# FPGA_SPI_JTAG_IO.net
KiCad netlist of a schematic drawn in Altium Designer
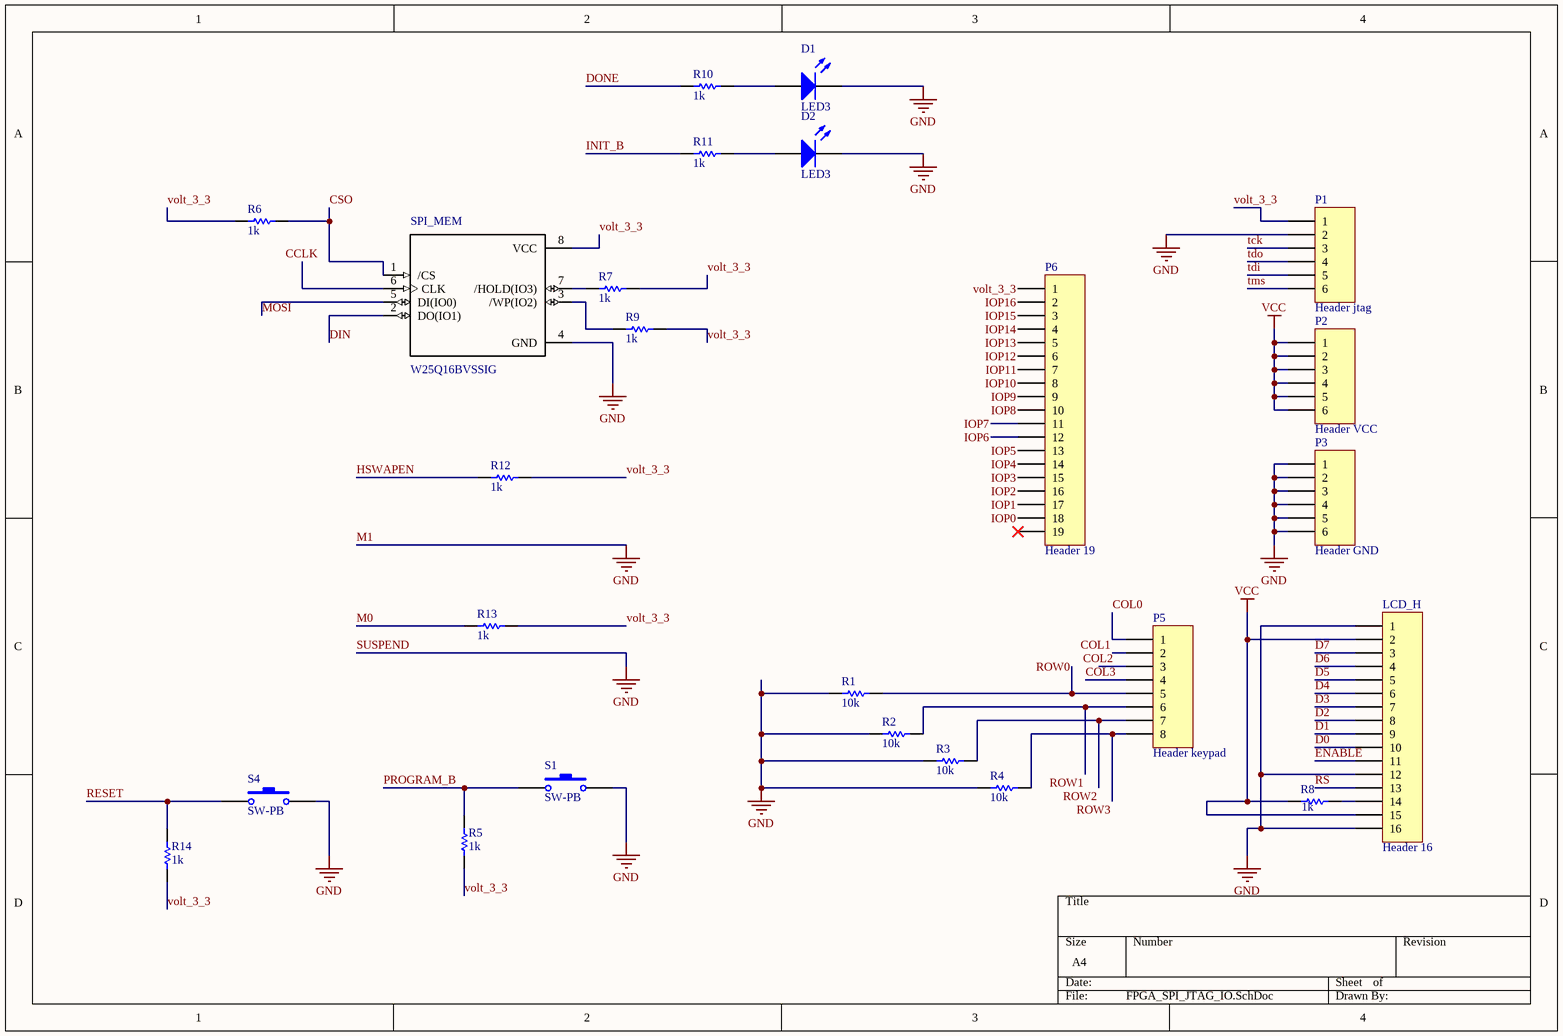
[diagram p0: FPGA_SPI_JTAG_IO.SchDoc]

(export (version "E")
  (design (tool "Eeschema 10.0.6"))
  (components
    (comp (ref "D1")
      (value "LED3")
      (footprint "3.5X2.8X1.9")
      (description "Typical BLUE SiC LED")
      (fields (field (name "PUBLISHER") "Altium Limited"))
      (libsource (lib "Miscellaneous Devices") (part "LED3"))
    )
    (comp (ref "D2")
      (value "LED3")
      (footprint "3.5X2.8X1.9")
      (description "Typical BLUE SiC LED")
      (fields (field (name "PUBLISHER") "Altium Limited"))
      (libsource (lib "Miscellaneous Devices") (part "LED3"))
    )
    (comp (ref "LCD_H")
      (value "Header 16")
      (footprint "HDR1X16")
      (description "Header, 16-Pin")
      (fields (field (name "PUBLISHER") "Altium Limited"))
      (libsource (lib "Miscellaneous Connectors") (part "Header 16"))
    )
    (comp (ref "P1")
      (value "Header jtag")
      (footprint "HDR1X6")
      (description "Header, 6-Pin")
      (fields (field (name "PUBLISHER") "Altium Limited"))
      (libsource (lib "Miscellaneous Connectors") (part "Header 6"))
    )
    (comp (ref "P2")
      (value "Header VCC")
      (footprint "HDR1X6")
      (description "Header, 6-Pin")
      (fields (field (name "PUBLISHER") "Altium Limited"))
      (libsource (lib "Miscellaneous Connectors") (part "Header 6"))
    )
    (comp (ref "P3")
      (value "Header GND")
      (footprint "HDR1X6")
      (description "Header, 6-Pin")
      (fields (field (name "PUBLISHER") "Altium Limited"))
      (libsource (lib "Miscellaneous Connectors") (part "Header 6"))
    )
    (comp (ref "P5")
      (value "Header keypad")
      (footprint "HDR1X8")
      (description "Header, 8-Pin")
      (fields (field (name "PUBLISHER") "Altium Limited"))
      (libsource (lib "Miscellaneous Connectors") (part "Header 8"))
    )
    (comp (ref "P6")
      (value "Header 19")
      (footprint "HDR1X19")
      (description "Header, 19-Pin")
      (fields (field (name "PUBLISHER") "Altium Limited"))
      (libsource (lib "Miscellaneous Connectors") (part "Header 19"))
    )
    (comp (ref "R1")
      (value "10k")
      (footprint "ERA-0805")
      (fields (field (name "PUBLISHER") "Altium Limited"))
      (libsource (lib "Panasonic Resistor") (part "ERA6Y"))
    )
    (comp (ref "R2")
      (value "10k")
      (footprint "ERA-0805")
      (fields (field (name "PUBLISHER") "Altium Limited"))
      (libsource (lib "Panasonic Resistor") (part "ERA6Y"))
    )
    (comp (ref "R3")
      (value "10k")
      (footprint "ERA-0805")
      (fields (field (name "PUBLISHER") "Altium Limited"))
      (libsource (lib "Panasonic Resistor") (part "ERA6Y"))
    )
    (comp (ref "R4")
      (value "10k")
      (footprint "ERA-0805")
      (fields (field (name "PUBLISHER") "Altium Limited"))
      (libsource (lib "Panasonic Resistor") (part "ERA6Y"))
    )
    (comp (ref "R5")
      (value "1k")
      (footprint "ERA-0805")
      (fields (field (name "PUBLISHER") "Altium Limited"))
      (libsource (lib "Panasonic Resistor") (part "ERA6Y"))
    )
    (comp (ref "R6")
      (value "1k")
      (footprint "ERA-0805")
      (fields (field (name "PUBLISHER") "Altium Limited"))
      (libsource (lib "Panasonic Resistor") (part "ERA6Y"))
    )
    (comp (ref "R7")
      (value "1k")
      (footprint "ERA-0805")
      (fields (field (name "PUBLISHER") "Altium Limited"))
      (libsource (lib "Panasonic Resistor") (part "ERA6Y"))
    )
    (comp (ref "R8")
      (value "1k")
      (footprint "ERA-0805")
      (fields (field (name "PUBLISHER") "Altium Limited"))
      (libsource (lib "Panasonic Resistor") (part "ERA6Y"))
    )
    (comp (ref "R9")
      (value "1k")
      (footprint "ERA-0805")
      (fields (field (name "PUBLISHER") "Altium Limited"))
      (libsource (lib "Panasonic Resistor") (part "ERA6Y"))
    )
    (comp (ref "R10")
      (value "1k")
      (footprint "ERA-0805")
      (fields (field (name "PUBLISHER") "Altium Limited"))
      (libsource (lib "Panasonic Resistor") (part "ERA6Y"))
    )
    (comp (ref "R11")
      (value "1k")
      (footprint "ERA-0805")
      (fields (field (name "PUBLISHER") "Altium Limited"))
      (libsource (lib "Panasonic Resistor") (part "ERA6Y"))
    )
    (comp (ref "R12")
      (value "1k")
      (footprint "ERA-0805")
      (fields (field (name "PUBLISHER") "Altium Limited"))
      (libsource (lib "Panasonic Resistor") (part "ERA6Y"))
    )
    (comp (ref "R13")
      (value "1k")
      (footprint "ERA-0805")
      (fields (field (name "PUBLISHER") "Altium Limited"))
      (libsource (lib "Panasonic Resistor") (part "ERA6Y"))
    )
    (comp (ref "R14")
      (value "1k")
      (footprint "ERA-0805")
      (fields (field (name "PUBLISHER") "Altium Limited"))
      (libsource (lib "Panasonic Resistor") (part "ERA6Y"))
    )
    (comp (ref "S1")
      (value "SW-PB")
      (footprint "SPST-2")
      (description "Switch")
      (fields (field (name "PUBLISHER") "Altium Limited"))
      (libsource (lib "Miscellaneous Devices") (part "SW-PB"))
    )
    (comp (ref "S4")
      (value "SW-PB")
      (footprint "SPST-2")
      (description "Switch")
      (fields (field (name "PUBLISHER") "Altium Limited"))
      (libsource (lib "Miscellaneous Devices") (part "SW-PB"))
    )
    (comp (ref "SPI_MEM")
      (value "W25Q16BVSSIG")
      (footprint "*SOIC127P790X216-8N")
      (description "Flash, pin, soic, flash, Memory, Semiconductors and Actives, serial, ic")
      (fields (field (name "MF") "Winbond") (field (name "DIGI-KEY_PART_NUMBER") "W25Q16BVSSIG-ND"))
      (libsource (lib "W25Q16BVSSIG") (part "W25Q16BVSSIG"))
    )
  )
  (nets
    (net (code "1") (name "/CCLK") (class "Default")
      (node (ref "SPI_MEM") (pin "6") (pinfunction "CLK_6") (pintype "input"))
    )
    (net (code "2") (name "/COL0") (class "Default")
      (node (ref "P5") (pin "1") (pinfunction "1_1") (pintype "passive"))
    )
    (net (code "3") (name "/COL1") (class "Default")
      (node (ref "P5") (pin "2") (pinfunction "2_2") (pintype "passive"))
    )
    (net (code "4") (name "/COL2") (class "Default")
      (node (ref "P5") (pin "3") (pinfunction "3_3") (pintype "passive"))
    )
    (net (code "5") (name "/COL3") (class "Default")
      (node (ref "P5") (pin "4") (pinfunction "4_4") (pintype "passive"))
    )
    (net (code "6") (name "/CSO") (class "Default")
      (node (ref "R6") (pin "2") (pinfunction "2_2") (pintype "passive"))
      (node (ref "SPI_MEM") (pin "1") (pinfunction "/CS_1") (pintype "input"))
    )
    (net (code "7") (name "/D0") (class "Default")
      (node (ref "LCD_H") (pin "10") (pinfunction "10_10") (pintype "passive"))
    )
    (net (code "8") (name "/D1") (class "Default")
      (node (ref "LCD_H") (pin "9") (pinfunction "9_9") (pintype "passive"))
    )
    (net (code "9") (name "/D2") (class "Default")
      (node (ref "LCD_H") (pin "8") (pinfunction "8_8") (pintype "passive"))
    )
    (net (code "10") (name "/D3") (class "Default")
      (node (ref "LCD_H") (pin "7") (pinfunction "7_7") (pintype "passive"))
    )
    (net (code "11") (name "/D4") (class "Default")
      (node (ref "LCD_H") (pin "6") (pinfunction "6_6") (pintype "passive"))
    )
    (net (code "12") (name "/D5") (class "Default")
      (node (ref "LCD_H") (pin "5") (pinfunction "5_5") (pintype "passive"))
    )
    (net (code "13") (name "/D6") (class "Default")
      (node (ref "LCD_H") (pin "4") (pinfunction "4_4") (pintype "passive"))
    )
    (net (code "14") (name "/D7") (class "Default")
      (node (ref "LCD_H") (pin "3") (pinfunction "3_3") (pintype "passive"))
    )
    (net (code "15") (name "/DIN") (class "Default")
      (node (ref "SPI_MEM") (pin "2") (pinfunction "DO(IO1)_2") (pintype "bidirectional"))
    )
    (net (code "16") (name "/DONE") (class "Default")
      (node (ref "R10") (pin "1") (pinfunction "1_1") (pintype "passive"))
    )
    (net (code "17") (name "/ENABLE") (class "Default")
      (node (ref "LCD_H") (pin "11") (pinfunction "11_11") (pintype "passive"))
    )
    (net (code "18") (name "/HSWAPEN") (class "Default")
      (node (ref "R12") (pin "2") (pinfunction "2_2") (pintype "passive"))
    )
    (net (code "19") (name "/INIT_B") (class "Default")
      (node (ref "R11") (pin "1") (pinfunction "1_1") (pintype "passive"))
    )
    (net (code "20") (name "/IOP0") (class "Default")
      (node (ref "P6") (pin "18") (pinfunction "18_18") (pintype "passive"))
    )
    (net (code "21") (name "/IOP1") (class "Default")
      (node (ref "P6") (pin "17") (pinfunction "17_17") (pintype "passive"))
    )
    (net (code "22") (name "/IOP2") (class "Default")
      (node (ref "P6") (pin "16") (pinfunction "16_16") (pintype "passive"))
    )
    (net (code "23") (name "/IOP3") (class "Default")
      (node (ref "P6") (pin "15") (pinfunction "15_15") (pintype "passive"))
    )
    (net (code "24") (name "/IOP4") (class "Default")
      (node (ref "P6") (pin "14") (pinfunction "14_14") (pintype "passive"))
    )
    (net (code "25") (name "/IOP5") (class "Default")
      (node (ref "P6") (pin "13") (pinfunction "13_13") (pintype "passive"))
    )
    (net (code "26") (name "/IOP6") (class "Default")
      (node (ref "P6") (pin "12") (pinfunction "12_12") (pintype "passive"))
    )
    (net (code "27") (name "/IOP7") (class "Default")
      (node (ref "P6") (pin "11") (pinfunction "11_11") (pintype "passive"))
    )
    (net (code "28") (name "/IOP8") (class "Default")
      (node (ref "P6") (pin "10") (pinfunction "10_10") (pintype "passive"))
    )
    (net (code "29") (name "/IOP9") (class "Default")
      (node (ref "P6") (pin "9") (pinfunction "9_9") (pintype "passive"))
    )
    (net (code "30") (name "/IOP10") (class "Default")
      (node (ref "P6") (pin "8") (pinfunction "8_8") (pintype "passive"))
    )
    (net (code "31") (name "/IOP11") (class "Default")
      (node (ref "P6") (pin "7") (pinfunction "7_7") (pintype "passive"))
    )
    (net (code "32") (name "/IOP12") (class "Default")
      (node (ref "P6") (pin "6") (pinfunction "6_6") (pintype "passive"))
    )
    (net (code "33") (name "/IOP13") (class "Default")
      (node (ref "P6") (pin "5") (pinfunction "5_5") (pintype "passive"))
    )
    (net (code "34") (name "/IOP14") (class "Default")
      (node (ref "P6") (pin "4") (pinfunction "4_4") (pintype "passive"))
    )
    (net (code "35") (name "/IOP15") (class "Default")
      (node (ref "P6") (pin "3") (pinfunction "3_3") (pintype "passive"))
    )
    (net (code "36") (name "/IOP16") (class "Default")
      (node (ref "P6") (pin "2") (pinfunction "2_2") (pintype "passive"))
    )
    (net (code "37") (name "/M0") (class "Default")
      (node (ref "R13") (pin "2") (pinfunction "2_2") (pintype "passive"))
    )
    (net (code "38") (name "/MOSI") (class "Default")
      (node (ref "SPI_MEM") (pin "5") (pinfunction "DI(IO0)_5") (pintype "bidirectional"))
    )
    (net (code "39") (name "/PROGRAM_B") (class "Default")
      (node (ref "R5") (pin "2") (pinfunction "2_2") (pintype "passive"))
      (node (ref "S1") (pin "1") (pinfunction "1_1") (pintype "passive"))
    )
    (net (code "40") (name "/RESET") (class "Default")
      (node (ref "R14") (pin "2") (pinfunction "2_2") (pintype "passive"))
      (node (ref "S4") (pin "1") (pinfunction "1_1") (pintype "passive"))
    )
    (net (code "41") (name "/ROW0") (class "Default")
      (node (ref "P5") (pin "5") (pinfunction "5_5") (pintype "passive"))
      (node (ref "R1") (pin "2") (pinfunction "2_2") (pintype "passive"))
    )
    (net (code "42") (name "/ROW1") (class "Default")
      (node (ref "P5") (pin "6") (pinfunction "6_6") (pintype "passive"))
      (node (ref "R2") (pin "2") (pinfunction "2_2") (pintype "passive"))
    )
    (net (code "43") (name "/ROW2") (class "Default")
      (node (ref "P5") (pin "7") (pinfunction "7_7") (pintype "passive"))
      (node (ref "R3") (pin "2") (pinfunction "2_2") (pintype "passive"))
    )
    (net (code "44") (name "/ROW3") (class "Default")
      (node (ref "P5") (pin "8") (pinfunction "8_8") (pintype "passive"))
      (node (ref "R4") (pin "2") (pinfunction "2_2") (pintype "passive"))
    )
    (net (code "45") (name "/RS") (class "Default")
      (node (ref "LCD_H") (pin "13") (pinfunction "13_13") (pintype "passive"))
    )
    (net (code "46") (name "/tck") (class "Default")
      (node (ref "P1") (pin "3") (pinfunction "3_3") (pintype "passive"))
    )
    (net (code "47") (name "/tdi") (class "Default")
      (node (ref "P1") (pin "5") (pinfunction "5_5") (pintype "passive"))
    )
    (net (code "48") (name "/tdo") (class "Default")
      (node (ref "P1") (pin "4") (pinfunction "4_4") (pintype "passive"))
    )
    (net (code "49") (name "/tms") (class "Default")
      (node (ref "P1") (pin "6") (pinfunction "6_6") (pintype "passive"))
    )
    (net (code "50") (name "/volt_3_3") (class "Default")
      (node (ref "P1") (pin "1") (pinfunction "1_1") (pintype "passive"))
      (node (ref "P6") (pin "1") (pinfunction "1_1") (pintype "passive"))
      (node (ref "R12") (pin "1") (pinfunction "1_1") (pintype "passive"))
      (node (ref "R13") (pin "1") (pinfunction "1_1") (pintype "passive"))
      (node (ref "R14") (pin "1") (pinfunction "1_1") (pintype "passive"))
      (node (ref "R5") (pin "1") (pinfunction "1_1") (pintype "passive"))
      (node (ref "R6") (pin "1") (pinfunction "1_1") (pintype "passive"))
      (node (ref "R7") (pin "1") (pinfunction "1_1") (pintype "passive"))
      (node (ref "R9") (pin "1") (pinfunction "1_1") (pintype "passive"))
      (node (ref "SPI_MEM") (pin "8") (pinfunction "VCC_8") (pintype "power_in"))
    )
    (net (code "51") (name "GND") (class "Default")
      (node (ref "D1") (pin "2") (pinfunction "K_2") (pintype "passive"))
      (node (ref "D2") (pin "2") (pinfunction "K_2") (pintype "passive"))
      (node (ref "LCD_H") (pin "1") (pinfunction "1_1") (pintype "passive"))
      (node (ref "LCD_H") (pin "12") (pinfunction "12_12") (pintype "passive"))
      (node (ref "LCD_H") (pin "16") (pinfunction "16_16") (pintype "passive"))
      (node (ref "P1") (pin "2") (pinfunction "2_2") (pintype "passive"))
      (node (ref "P3") (pin "1") (pinfunction "1_1") (pintype "passive"))
      (node (ref "P3") (pin "2") (pinfunction "2_2") (pintype "passive"))
      (node (ref "P3") (pin "3") (pinfunction "3_3") (pintype "passive"))
      (node (ref "P3") (pin "4") (pinfunction "4_4") (pintype "passive"))
      (node (ref "P3") (pin "5") (pinfunction "5_5") (pintype "passive"))
      (node (ref "P3") (pin "6") (pinfunction "6_6") (pintype "passive"))
      (node (ref "R1") (pin "1") (pinfunction "1_1") (pintype "passive"))
      (node (ref "R2") (pin "1") (pinfunction "1_1") (pintype "passive"))
      (node (ref "R3") (pin "1") (pinfunction "1_1") (pintype "passive"))
      (node (ref "R4") (pin "1") (pinfunction "1_1") (pintype "passive"))
      (node (ref "S1") (pin "2") (pinfunction "2_2") (pintype "passive"))
      (node (ref "S4") (pin "2") (pinfunction "2_2") (pintype "passive"))
      (node (ref "SPI_MEM") (pin "4") (pinfunction "GND_4") (pintype "power_in"))
    )
    (net (code "52") (name "Net-(D1-A)") (class "Default")
      (node (ref "D1") (pin "1") (pinfunction "A_1") (pintype "passive"))
      (node (ref "R10") (pin "2") (pinfunction "2_2") (pintype "passive"))
    )
    (net (code "53") (name "Net-(D2-A)") (class "Default")
      (node (ref "D2") (pin "1") (pinfunction "A_1") (pintype "passive"))
      (node (ref "R11") (pin "2") (pinfunction "2_2") (pintype "passive"))
    )
    (net (code "54") (name "Net-(LCD_H-Pad14)") (class "Default")
      (node (ref "LCD_H") (pin "14") (pinfunction "14_14") (pintype "passive"))
      (node (ref "R8") (pin "2") (pinfunction "2_2") (pintype "passive"))
    )
    (net (code "55") (name "Net-(SPI_MEM-{slash}HOLD(IO3))") (class "Default")
      (node (ref "R7") (pin "2") (pinfunction "2_2") (pintype "passive"))
      (node (ref "SPI_MEM") (pin "7") (pinfunction "/HOLD(IO3)_7") (pintype "bidirectional"))
    )
    (net (code "56") (name "Net-(SPI_MEM-{slash}WP(IO2))") (class "Default")
      (node (ref "R9") (pin "2") (pinfunction "2_2") (pintype "passive"))
      (node (ref "SPI_MEM") (pin "3") (pinfunction "/WP(IO2)_3") (pintype "bidirectional"))
    )
    (net (code "57") (name "VCC") (class "Default")
      (node (ref "LCD_H") (pin "15") (pinfunction "15_15") (pintype "passive"))
      (node (ref "LCD_H") (pin "2") (pinfunction "2_2") (pintype "passive"))
      (node (ref "P2") (pin "1") (pinfunction "1_1") (pintype "passive"))
      (node (ref "P2") (pin "2") (pinfunction "2_2") (pintype "passive"))
      (node (ref "P2") (pin "3") (pinfunction "3_3") (pintype "passive"))
      (node (ref "P2") (pin "4") (pinfunction "4_4") (pintype "passive"))
      (node (ref "P2") (pin "5") (pinfunction "5_5") (pintype "passive"))
      (node (ref "P2") (pin "6") (pinfunction "6_6") (pintype "passive"))
      (node (ref "R8") (pin "1") (pinfunction "1_1") (pintype "passive"))
    )
    (net (code "58") (name "unconnected-(P6-Pad19)") (class "Default")
      (node (ref "P6") (pin "19") (pinfunction "19_19") (pintype "passive+no_connect"))
    )
  )
)
